# clock.net
KiCad netlist of a schematic drawn in EAGLE
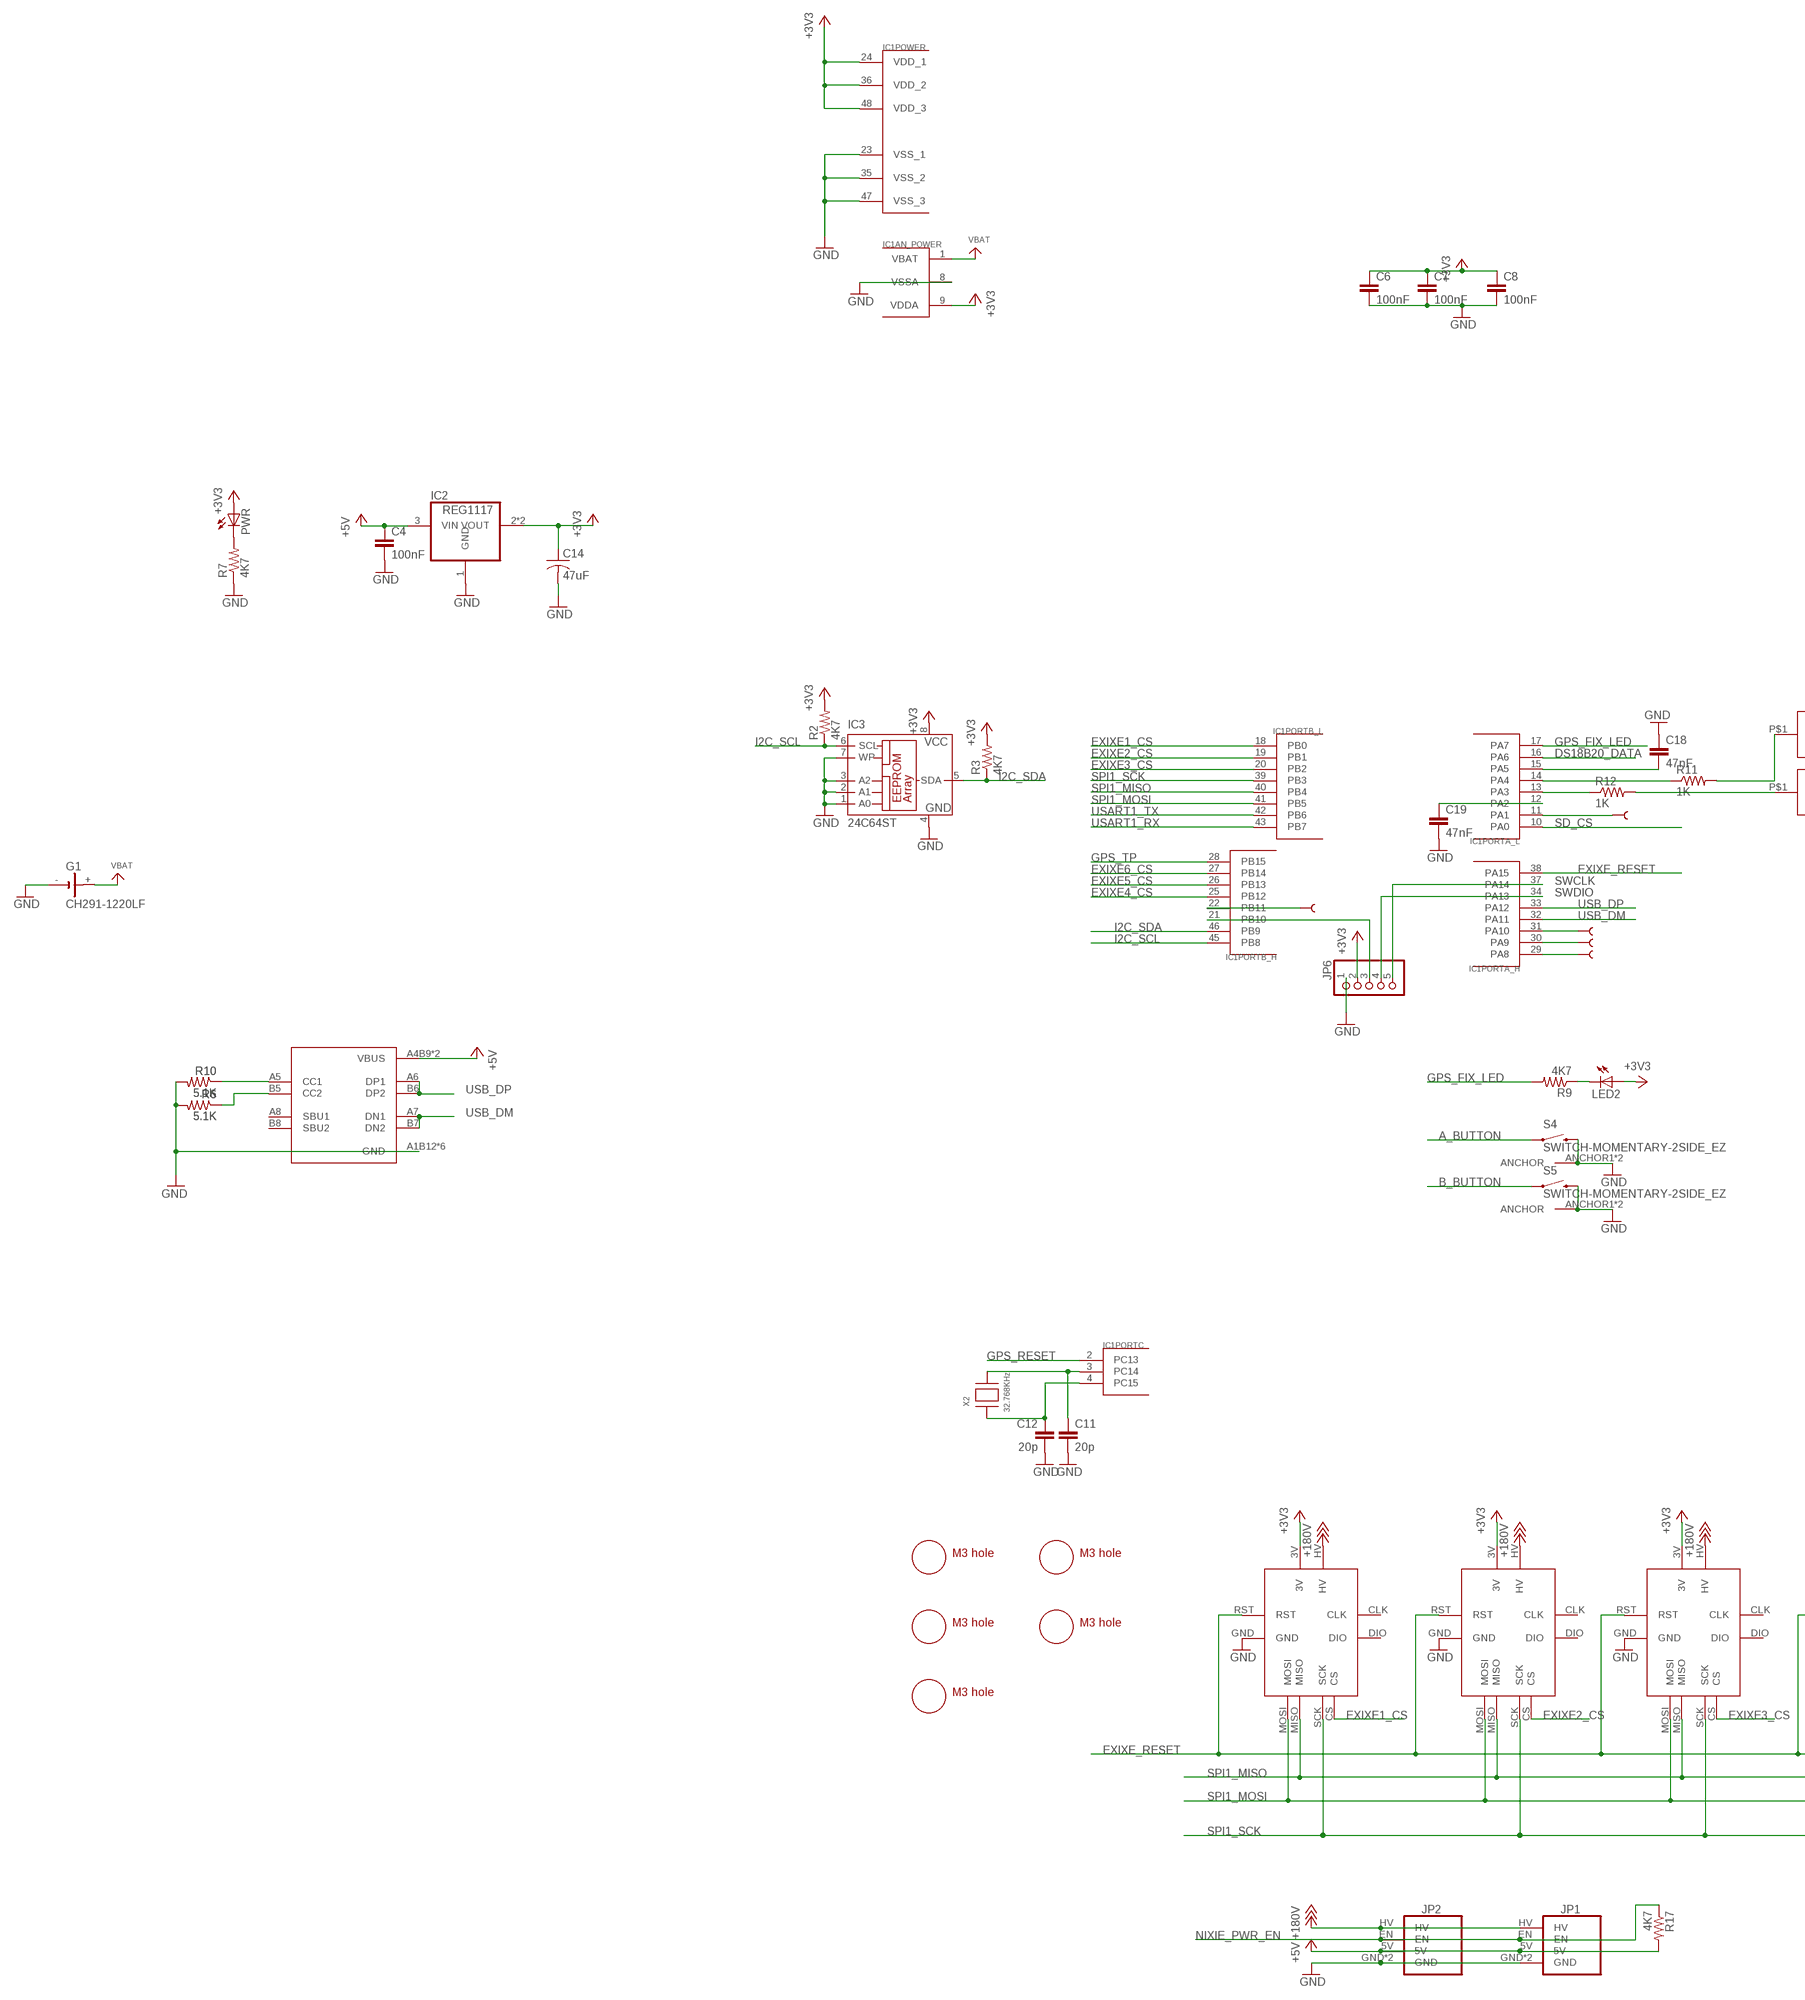
[diagram p0: schematic, sheet 1, part 1 of 2]
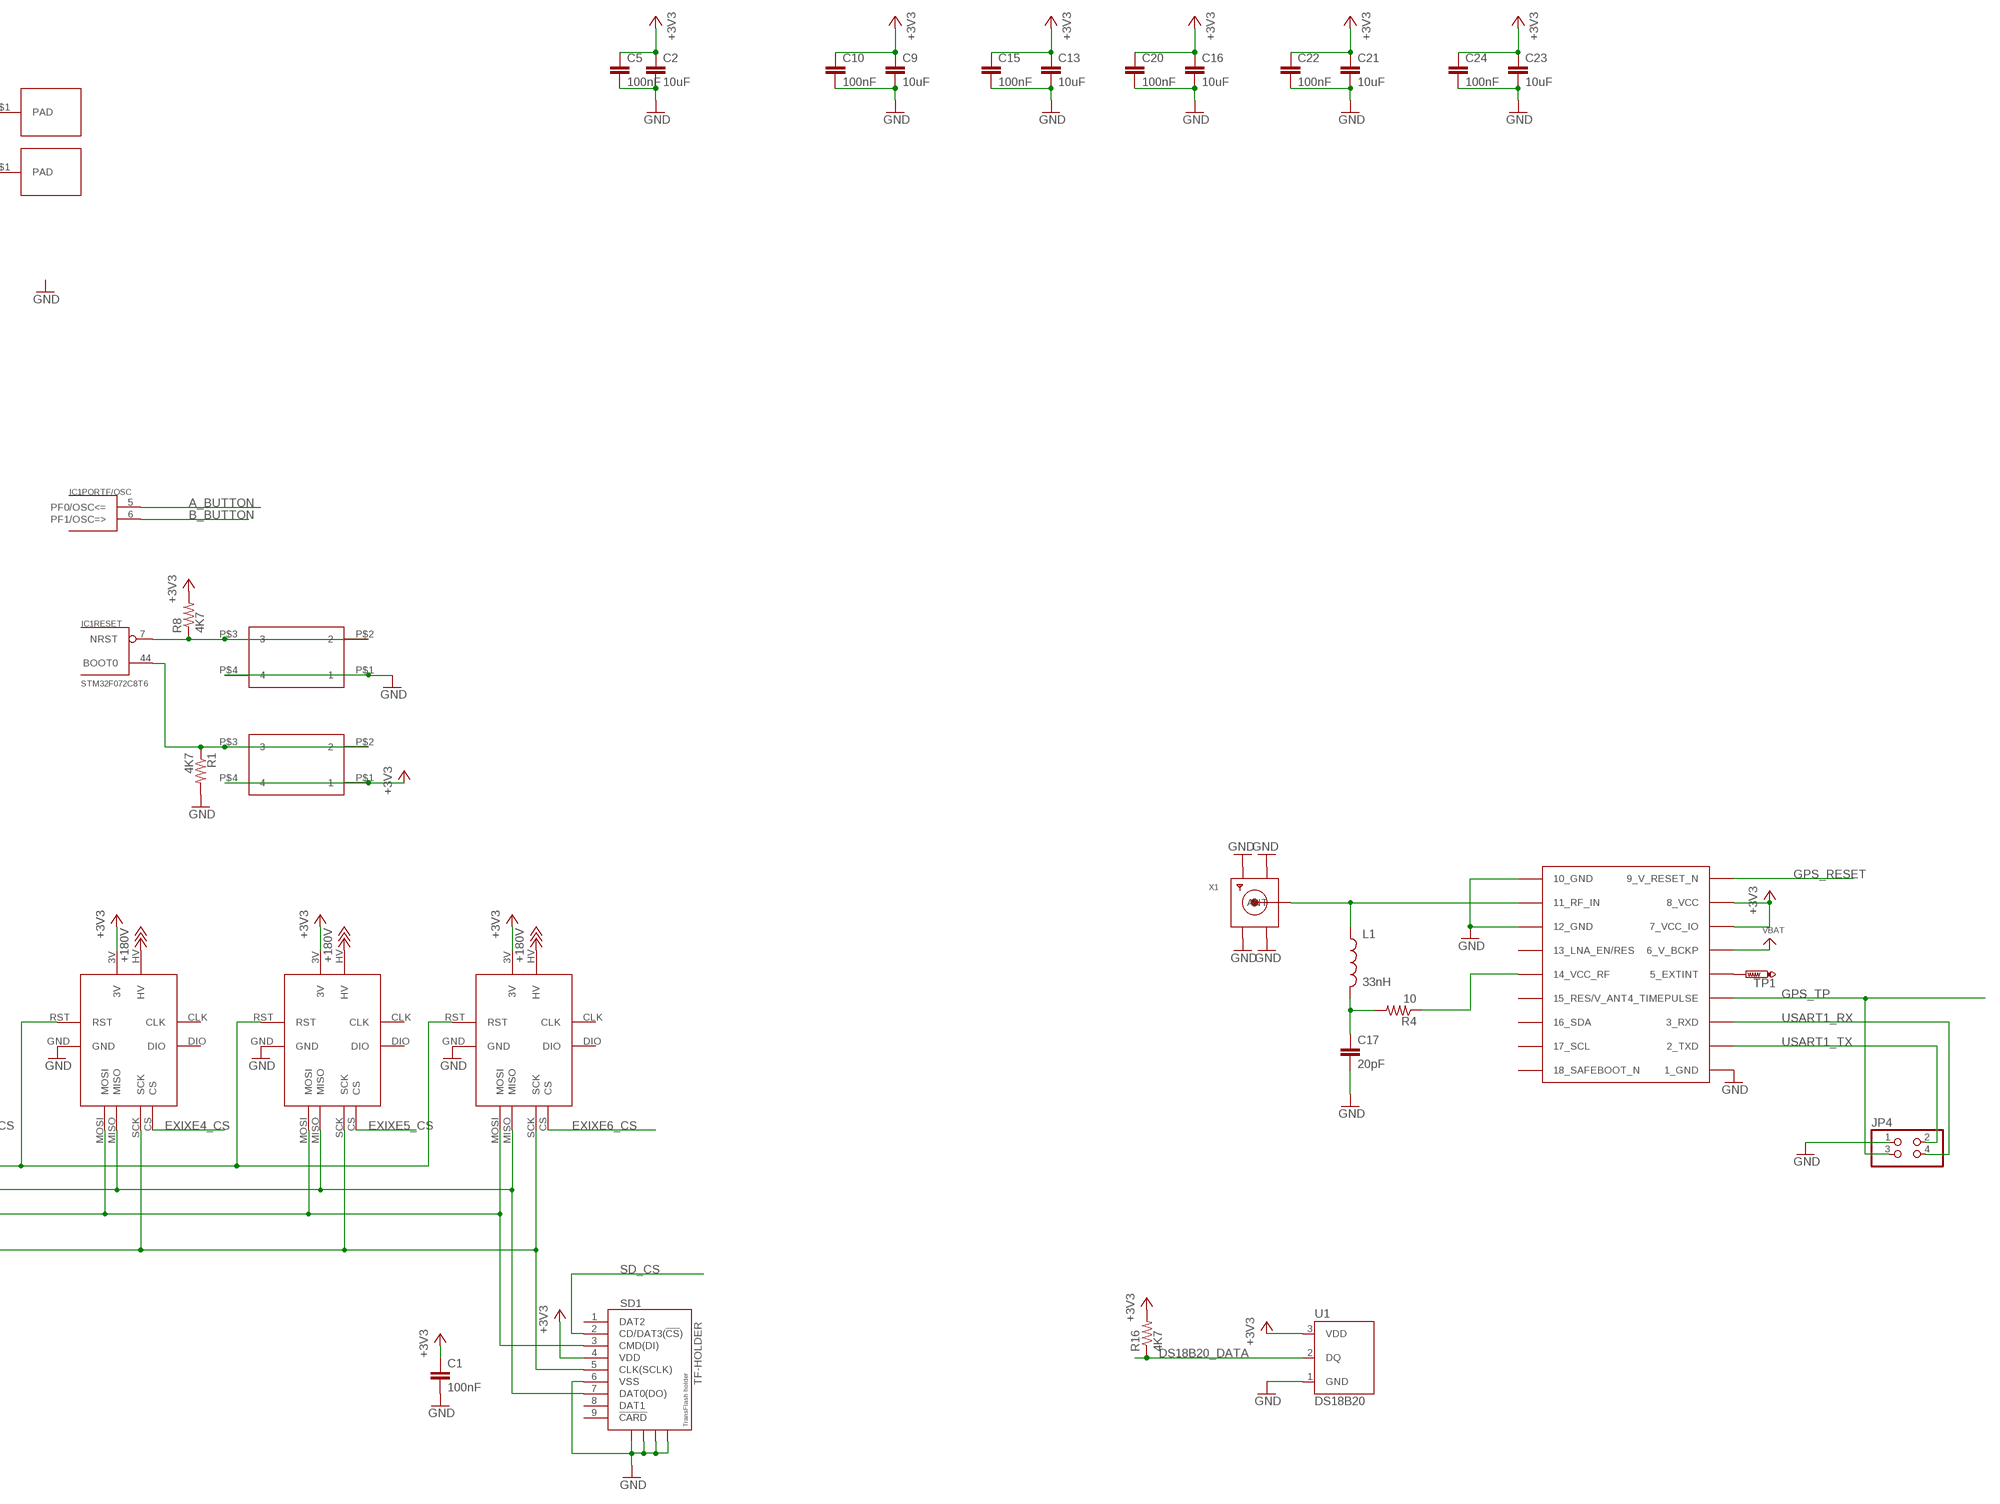
[diagram p1: schematic, sheet 1, part 2 of 2]

(export (version "E")
  (design (tool "Eeschema 10.0.6"))
  (components
    (comp (ref "C1")
      (value "100nF")
      (footprint "eagle-import:0805")
      (libsource (lib "eagle-import") (part "CAP0805"))
    )
    (comp (ref "C2")
      (value "10uF")
      (footprint "eagle-import:0805")
      (libsource (lib "eagle-import") (part "CAP0805"))
    )
    (comp (ref "C4")
      (value "100nF")
      (footprint "eagle-import:0805")
      (libsource (lib "eagle-import") (part "CAP0805"))
    )
    (comp (ref "C5")
      (value "100nF")
      (footprint "eagle-import:0805")
      (libsource (lib "eagle-import") (part "CAP0805"))
    )
    (comp (ref "C6")
      (value "100nF")
      (footprint "eagle-import:0805")
      (libsource (lib "eagle-import") (part "CAP0805"))
    )
    (comp (ref "C7")
      (value "100nF")
      (footprint "eagle-import:0805")
      (libsource (lib "eagle-import") (part "CAP0805"))
    )
    (comp (ref "C8")
      (value "100nF")
      (footprint "eagle-import:0805")
      (libsource (lib "eagle-import") (part "CAP0805"))
    )
    (comp (ref "C9")
      (value "10uF")
      (footprint "eagle-import:0805")
      (libsource (lib "eagle-import") (part "CAP0805"))
    )
    (comp (ref "C10")
      (value "100nF")
      (footprint "eagle-import:0805")
      (libsource (lib "eagle-import") (part "CAP0805"))
    )
    (comp (ref "C11")
      (value "20p")
      (footprint "eagle-import:0805")
      (libsource (lib "eagle-import") (part "CAP0805"))
    )
    (comp (ref "C12")
      (value "20p")
      (footprint "eagle-import:0805")
      (libsource (lib "eagle-import") (part "CAP0805"))
    )
    (comp (ref "C13")
      (value "10uF")
      (footprint "eagle-import:0805")
      (libsource (lib "eagle-import") (part "CAP0805"))
    )
    (comp (ref "C14")
      (value "47uF")
      (footprint "eagle-import:C1210")
      (libsource (lib "eagle-import") (part "C-USC1210"))
    )
    (comp (ref "C15")
      (value "100nF")
      (footprint "eagle-import:0805")
      (libsource (lib "eagle-import") (part "CAP0805"))
    )
    (comp (ref "C16")
      (value "10uF")
      (footprint "eagle-import:0805")
      (libsource (lib "eagle-import") (part "CAP0805"))
    )
    (comp (ref "C17")
      (value "20pF")
      (footprint "eagle-import:0805")
      (libsource (lib "eagle-import") (part "CAP0805"))
    )
    (comp (ref "C18")
      (value "47nF")
      (footprint "eagle-import:0805")
      (libsource (lib "eagle-import") (part "CAP0805"))
    )
    (comp (ref "C19")
      (value "47nF")
      (footprint "eagle-import:0805")
      (libsource (lib "eagle-import") (part "CAP0805"))
    )
    (comp (ref "C20")
      (value "100nF")
      (footprint "eagle-import:0805")
      (libsource (lib "eagle-import") (part "CAP0805"))
    )
    (comp (ref "C21")
      (value "10uF")
      (footprint "eagle-import:0805")
      (libsource (lib "eagle-import") (part "CAP0805"))
    )
    (comp (ref "C22")
      (value "100nF")
      (footprint "eagle-import:0805")
      (libsource (lib "eagle-import") (part "CAP0805"))
    )
    (comp (ref "C23")
      (value "10uF")
      (footprint "eagle-import:0805")
      (libsource (lib "eagle-import") (part "CAP0805"))
    )
    (comp (ref "C24")
      (value "100nF")
      (footprint "eagle-import:0805")
      (libsource (lib "eagle-import") (part "CAP0805"))
    )
    (comp (ref "G1")
      (value "CH291-1220LF")
      (footprint "eagle-import:CH291-1220LF")
      (libsource (lib "eagle-import") (part "CH291-1220LF"))
    )
    (comp (ref "IC1")
      (value "STM32F072C8T6")
      (footprint "eagle-import:TQFP48")
      (libsource (lib "eagle-import") (part "STM32F072C8T6"))
    )
    (comp (ref "IC2")
      (value "REG1117")
      (footprint "eagle-import:SOT223")
      (libsource (lib "eagle-import") (part "REG1117"))
    )
    (comp (ref "IC3")
      (value "24C64ST")
      (footprint "eagle-import:TSSOP8")
      (fields (field (name "MPN") "CAT24C64YI-GT3"))
      (libsource (lib "eagle-import") (part "24STC64"))
    )
    (comp (ref "JP1")
      (value "EBAY_MODULEEBAY")
      (footprint "eagle-import:EBAY_PKG")
      (libsource (lib "eagle-import") (part "EBAY_MODULEEBAY"))
    )
    (comp (ref "JP2")
      (value "EBAY_MODULETAOBAO")
      (footprint "eagle-import:TAOBAO_PKG")
      (libsource (lib "eagle-import") (part "EBAY_MODULETAOBAO"))
    )
    (comp (ref "JP4")
      (value "PINHD-2X2")
      (footprint "eagle-import:2X02")
      (libsource (lib "eagle-import") (part "PINHD-2X2"))
    )
    (comp (ref "JP6")
      (value "PINHD-1X5")
      (footprint "eagle-import:1X05")
      (libsource (lib "eagle-import") (part "PINHD-1X5"))
    )
    (comp (ref "L1")
      (value "33nH")
      (footprint "eagle-import:0805")
      (libsource (lib "eagle-import") (part "INDUCTOR0805"))
    )
    (comp (ref "LED2")
      (value "LEDCHIP-LED0805")
      (footprint "eagle-import:CHIP-LED0805")
      (libsource (lib "eagle-import") (part "LEDCHIP-LED0805"))
    )
    (comp (ref "PWR")
      (value "LEDCHIP-LED0805")
      (footprint "eagle-import:CHIP-LED0805")
      (libsource (lib "eagle-import") (part "LEDCHIP-LED0805"))
    )
    (comp (ref "R1")
      (value "4K7")
      (footprint "eagle-import:0805")
      (libsource (lib "eagle-import") (part "RESISTOR0805-RES"))
    )
    (comp (ref "R2")
      (value "4K7")
      (footprint "eagle-import:0805")
      (libsource (lib "eagle-import") (part "RESISTOR0805-RES"))
    )
    (comp (ref "R3")
      (value "4K7")
      (footprint "eagle-import:0805")
      (libsource (lib "eagle-import") (part "RESISTOR0805-RES"))
    )
    (comp (ref "R4")
      (value "10")
      (footprint "eagle-import:0805")
      (libsource (lib "eagle-import") (part "RESISTOR0805-RES"))
    )
    (comp (ref "R6")
      (value "5.1K")
      (footprint "eagle-import:0805")
      (libsource (lib "eagle-import") (part "joyAnalog_RESISTOR0805-RES"))
    )
    (comp (ref "R7")
      (value "4K7")
      (footprint "eagle-import:0805")
      (libsource (lib "eagle-import") (part "RESISTOR0805-RES"))
    )
    (comp (ref "R8")
      (value "4K7")
      (footprint "eagle-import:0805")
      (libsource (lib "eagle-import") (part "RESISTOR0805-RES"))
    )
    (comp (ref "R9")
      (value "4K7")
      (footprint "eagle-import:0805")
      (libsource (lib "eagle-import") (part "RESISTOR0805-RES"))
    )
    (comp (ref "R10")
      (value "5.1K")
      (footprint "eagle-import:0805")
      (libsource (lib "eagle-import") (part "joyAnalog_RESISTOR0805-RES"))
    )
    (comp (ref "R11")
      (value "1K")
      (footprint "eagle-import:0805")
      (libsource (lib "eagle-import") (part "RESISTOR0805-RES"))
    )
    (comp (ref "R12")
      (value "1K")
      (footprint "eagle-import:0805")
      (libsource (lib "eagle-import") (part "RESISTOR0805-RES"))
    )
    (comp (ref "R16")
      (value "4K7")
      (footprint "eagle-import:0805")
      (libsource (lib "eagle-import") (part "RESISTOR0805-RES"))
    )
    (comp (ref "R17")
      (value "4K7")
      (footprint "eagle-import:0805")
      (libsource (lib "eagle-import") (part "RESISTOR0805-RES"))
    )
    (comp (ref "S4")
      (value "SWITCH-MOMENTARY-2SIDE_EZ")
      (footprint "eagle-import:TACTILE-PTH-SIDEEZ")
      (libsource (lib "eagle-import") (part "SWITCH-MOMENTARY-2SIDE_EZ"))
    )
    (comp (ref "S5")
      (value "SWITCH-MOMENTARY-2SIDE_EZ")
      (footprint "eagle-import:TACTILE-PTH-SIDEEZ")
      (libsource (lib "eagle-import") (part "SWITCH-MOMENTARY-2SIDE_EZ"))
    )
    (comp (ref "SD1")
      (value "TF-HOLDER")
      (footprint "eagle-import:TF-PULL")
      (libsource (lib "eagle-import") (part "TF-HOLDER"))
    )
    (comp (ref "SW1")
      (value "324_SW324_SWITCH_FOOT_HOLE")
      (footprint "eagle-import:342_SWICH_FOOT_HOLE")
      (libsource (lib "eagle-import") (part "324_SW324_SWITCH_FOOT_HOLE"))
    )
    (comp (ref "SW4")
      (value "324_SW324_SWITCH_FOOT_HOLE")
      (footprint "eagle-import:342_SWICH_FOOT_HOLE")
      (libsource (lib "eagle-import") (part "324_SW324_SWITCH_FOOT_HOLE"))
    )
    (comp (ref "TP1")
      (value "PTR1TP20R")
      (footprint "eagle-import:TP20R")
      (libsource (lib "eagle-import") (part "PTR1TP20R"))
    )
    (comp (ref "TP2")
      (value "TEST-POINT3X5")
      (footprint "eagle-import:PAD.03X.05")
      (libsource (lib "eagle-import") (part "TEST-POINT3X5"))
    )
    (comp (ref "TP3")
      (value "TEST-POINT3X5")
      (footprint "eagle-import:PAD.03X.05")
      (libsource (lib "eagle-import") (part "TEST-POINT3X5"))
    )
    (comp (ref "TP4")
      (value "TEST-POINT3X5")
      (footprint "eagle-import:PAD.03X.05")
      (libsource (lib "eagle-import") (part "TEST-POINT3X5"))
    )
    (comp (ref "TP5")
      (value "TEST-POINT3X5")
      (footprint "eagle-import:PAD.03X.05")
      (libsource (lib "eagle-import") (part "TEST-POINT3X5"))
    )
    (comp (ref "TP6")
      (value "TEST-POINT3X5")
      (footprint "eagle-import:PAD.03X.05")
      (libsource (lib "eagle-import") (part "TEST-POINT3X5"))
    )
    (comp (ref "U$1")
      (value "EXIXE")
      (footprint "eagle-import:EXIXE_PAC")
      (libsource (lib "eagle-import") (part "EXIXE"))
    )
    (comp (ref "U$2")
      (value "EXIXE")
      (footprint "eagle-import:EXIXE_PAC")
      (libsource (lib "eagle-import") (part "EXIXE"))
    )
    (comp (ref "U$3")
      (value "EXIXE")
      (footprint "eagle-import:EXIXE_PAC")
      (libsource (lib "eagle-import") (part "EXIXE"))
    )
    (comp (ref "U$4")
      (value "EXIXE")
      (footprint "eagle-import:EXIXE_PAC")
      (libsource (lib "eagle-import") (part "EXIXE"))
    )
    (comp (ref "U$5")
      (value "EXIXE")
      (footprint "eagle-import:EXIXE_PAC")
      (libsource (lib "eagle-import") (part "EXIXE"))
    )
    (comp (ref "U$6")
      (value "EXIXE")
      (footprint "eagle-import:EXIXE_PAC")
      (libsource (lib "eagle-import") (part "EXIXE"))
    )
    (comp (ref "U$7")
      (value "MAX-M8")
      (footprint "eagle-import:MAX-M8")
      (libsource (lib "eagle-import") (part "MAX-M8"))
    )
    (comp (ref "U$10")
      (value "M3_MOUNTING_HOLE")
      (footprint "eagle-import:M3_MOUNTING_HOLE_PACK")
      (libsource (lib "eagle-import") (part "M3_MOUNTING_HOLE"))
    )
    (comp (ref "U$11")
      (value "M3_MOUNTING_HOLE")
      (footprint "eagle-import:M3_MOUNTING_HOLE_PACK")
      (libsource (lib "eagle-import") (part "M3_MOUNTING_HOLE"))
    )
    (comp (ref "U$12")
      (value "M3_MOUNTING_HOLE")
      (footprint "eagle-import:M3_MOUNTING_HOLE_PACK")
      (libsource (lib "eagle-import") (part "M3_MOUNTING_HOLE"))
    )
    (comp (ref "U$13")
      (value "M3_MOUNTING_HOLE")
      (footprint "eagle-import:M3_MOUNTING_HOLE_PACK")
      (libsource (lib "eagle-import") (part "M3_MOUNTING_HOLE"))
    )
    (comp (ref "U$14")
      (value "TOUCHPAD")
      (footprint "eagle-import:TOUCHPAD_PAK")
      (libsource (lib "eagle-import") (part "TOUCHPAD"))
    )
    (comp (ref "U$15")
      (value "TOUCHPAD")
      (footprint "eagle-import:TOUCHPAD_PAK")
      (libsource (lib "eagle-import") (part "TOUCHPAD"))
    )
    (comp (ref "U$20")
      (value "M3_MOUNTING_HOLE")
      (footprint "eagle-import:M3_MOUNTING_HOLE_PACK")
      (libsource (lib "eagle-import") (part "M3_MOUNTING_HOLE"))
    )
    (comp (ref "U1")
      (value "DS18B20")
      (footprint "eagle-import:TO-92-AMMO")
      (libsource (lib "eagle-import") (part "DS18B20"))
    )
    (comp (ref "U2")
      (value "USBC_16P")
      (footprint "eagle-import:USBC_16P_FOOT")
      (libsource (lib "eagle-import") (part "USBC_16P"))
    )
    (comp (ref "X1")
      (value "SMACONNECTOR")
      (footprint "eagle-import:SMA90_DIP")
      (libsource (lib "eagle-import") (part "SMACONNECTOR"))
    )
    (comp (ref "X2")
      (value "32.768KHz")
      (footprint "eagle-import:XTAL3215")
      (libsource (lib "eagle-import") (part "XTAL-3.2X1.5"))
    )
  )
  (nets
    (net (code "1") (name "+3V3") (class "Default")
      (node (ref "C1") (pin "1") (pinfunction "1_1") (pintype "passive"))
      (node (ref "C10") (pin "1") (pinfunction "1_1") (pintype "passive"))
      (node (ref "C13") (pin "1") (pinfunction "1_1") (pintype "passive"))
      (node (ref "C14") (pin "1") (pinfunction "1_1") (pintype "passive"))
      (node (ref "C15") (pin "1") (pinfunction "1_1") (pintype "passive"))
      (node (ref "C16") (pin "1") (pinfunction "1_1") (pintype "passive"))
      (node (ref "C2") (pin "1") (pinfunction "1_1") (pintype "passive"))
      (node (ref "C20") (pin "1") (pinfunction "1_1") (pintype "passive"))
      (node (ref "C21") (pin "1") (pinfunction "1_1") (pintype "passive"))
      (node (ref "C22") (pin "1") (pinfunction "1_1") (pintype "passive"))
      (node (ref "C23") (pin "1") (pinfunction "1_1") (pintype "passive"))
      (node (ref "C24") (pin "1") (pinfunction "1_1") (pintype "passive"))
      (node (ref "C5") (pin "1") (pinfunction "1_1") (pintype "passive"))
      (node (ref "C6") (pin "1") (pinfunction "1_1") (pintype "passive"))
      (node (ref "C7") (pin "1") (pinfunction "1_1") (pintype "passive"))
      (node (ref "C8") (pin "1") (pinfunction "1_1") (pintype "passive"))
      (node (ref "C9") (pin "1") (pinfunction "1_1") (pintype "passive"))
      (node (ref "IC1") (pin "24") (pinfunction "VDD_1_24") (pintype "power_in"))
      (node (ref "IC1") (pin "36") (pinfunction "VDD_2_36") (pintype "power_in"))
      (node (ref "IC1") (pin "48") (pinfunction "VDD_3_48") (pintype "power_in"))
      (node (ref "IC1") (pin "9") (pinfunction "VDDA_9") (pintype "power_in"))
      (node (ref "IC2") (pin "2") (pinfunction "VOUT_2") (pintype "output"))
      (node (ref "IC2") (pin "4") (pinfunction "VOUT_4") (pintype "output"))
      (node (ref "IC3") (pin "8") (pinfunction "VCC_8") (pintype "power_in"))
      (node (ref "JP6") (pin "2") (pinfunction "2_2") (pintype "passive"))
      (node (ref "LED2") (pin "A") (pinfunction "A_A") (pintype "passive"))
      (node (ref "PWR") (pin "A") (pinfunction "A_A") (pintype "passive"))
      (node (ref "R16") (pin "2") (pinfunction "2_2") (pintype "passive"))
      (node (ref "R2") (pin "2") (pinfunction "2_2") (pintype "passive"))
      (node (ref "R3") (pin "2") (pinfunction "2_2") (pintype "passive"))
      (node (ref "R8") (pin "2") (pinfunction "2_2") (pintype "passive"))
      (node (ref "SD1") (pin "4") (pinfunction "VDD_4") (pintype "power_in"))
      (node (ref "SW1") (pin "P$1") (pinfunction "1_P$1") (pintype "bidirectional"))
      (node (ref "SW1") (pin "P$4") (pinfunction "4_P$4") (pintype "bidirectional"))
      (node (ref "U$1") (pin "3V") (pinfunction "3V_3V") (pintype "bidirectional"))
      (node (ref "U$2") (pin "3V") (pinfunction "3V_3V") (pintype "bidirectional"))
      (node (ref "U$3") (pin "3V") (pinfunction "3V_3V") (pintype "bidirectional"))
      (node (ref "U$4") (pin "3V") (pinfunction "3V_3V") (pintype "bidirectional"))
      (node (ref "U$5") (pin "3V") (pinfunction "3V_3V") (pintype "bidirectional"))
      (node (ref "U$6") (pin "3V") (pinfunction "3V_3V") (pintype "bidirectional"))
      (node (ref "U$7") (pin "7_VCC_IO") (pinfunction "7_VCC_IO_7_VCC_IO") (pintype "power_in"))
      (node (ref "U$7") (pin "8_VCC") (pinfunction "8_VCC_8_VCC") (pintype "power_in"))
      (node (ref "U1") (pin "3") (pinfunction "VDD_3") (pintype "power_in"))
    )
    (net (code "2") (name "+5V") (class "Default")
      (node (ref "C4") (pin "1") (pinfunction "1_1") (pintype "passive"))
      (node (ref "IC2") (pin "3") (pinfunction "VIN_3") (pintype "input"))
      (node (ref "JP1") (pin "5V") (pinfunction "5V_5V") (pintype "bidirectional"))
      (node (ref "JP2") (pin "5V") (pinfunction "5V_5V") (pintype "bidirectional"))
      (node (ref "R17") (pin "2") (pinfunction "2_2") (pintype "passive"))
      (node (ref "U2") (pin "A4B9") (pinfunction "VBUS_A4B9") (pintype "bidirectional"))
      (node (ref "U2") (pin "B4A9") (pinfunction "VBUS_B4A9") (pintype "bidirectional"))
    )
    (net (code "3") (name "+180V") (class "Default")
      (node (ref "JP1") (pin "HV") (pinfunction "HV_HV") (pintype "bidirectional"))
      (node (ref "JP2") (pin "HV") (pinfunction "HV_HV") (pintype "bidirectional"))
      (node (ref "U$1") (pin "HV") (pinfunction "HV_HV") (pintype "bidirectional"))
      (node (ref "U$2") (pin "HV") (pinfunction "HV_HV") (pintype "bidirectional"))
      (node (ref "U$3") (pin "HV") (pinfunction "HV_HV") (pintype "bidirectional"))
      (node (ref "U$4") (pin "HV") (pinfunction "HV_HV") (pintype "bidirectional"))
      (node (ref "U$5") (pin "HV") (pinfunction "HV_HV") (pintype "bidirectional"))
      (node (ref "U$6") (pin "HV") (pinfunction "HV_HV") (pintype "bidirectional"))
    )
    (net (code "4") (name "/A_BUTTON") (class "Default")
      (node (ref "IC1") (pin "5") (pinfunction "PF0/OSC<=_5") (pintype "bidirectional"))
      (node (ref "S4") (pin "1") (pinfunction "1_1") (pintype "passive"))
    )
    (net (code "5") (name "/B_BUTTON") (class "Default")
      (node (ref "IC1") (pin "6") (pinfunction "PF1/OSC=>_6") (pintype "bidirectional"))
      (node (ref "S5") (pin "1") (pinfunction "1_1") (pintype "passive"))
    )
    (net (code "6") (name "/DS18B20_DATA") (class "Default")
      (node (ref "IC1") (pin "16") (pinfunction "PA6_16") (pintype "bidirectional"))
      (node (ref "R16") (pin "1") (pinfunction "1_1") (pintype "passive"))
      (node (ref "U1") (pin "2") (pinfunction "DQ_2") (pintype "bidirectional"))
    )
    (net (code "7") (name "/EXIXE1_CS") (class "Default")
      (node (ref "IC1") (pin "18") (pinfunction "PB0_18") (pintype "bidirectional"))
      (node (ref "U$1") (pin "CS") (pinfunction "CS_CS") (pintype "bidirectional"))
    )
    (net (code "8") (name "/EXIXE2_CS") (class "Default")
      (node (ref "IC1") (pin "19") (pinfunction "PB1_19") (pintype "bidirectional"))
      (node (ref "U$2") (pin "CS") (pinfunction "CS_CS") (pintype "bidirectional"))
    )
    (net (code "9") (name "/EXIXE3_CS") (class "Default")
      (node (ref "IC1") (pin "20") (pinfunction "PB2_20") (pintype "bidirectional"))
      (node (ref "U$3") (pin "CS") (pinfunction "CS_CS") (pintype "bidirectional"))
    )
    (net (code "10") (name "/EXIXE4_CS") (class "Default")
      (node (ref "IC1") (pin "25") (pinfunction "PB12_25") (pintype "bidirectional"))
      (node (ref "U$4") (pin "CS") (pinfunction "CS_CS") (pintype "bidirectional"))
    )
    (net (code "11") (name "/EXIXE5_CS") (class "Default")
      (node (ref "IC1") (pin "26") (pinfunction "PB13_26") (pintype "bidirectional"))
      (node (ref "U$5") (pin "CS") (pinfunction "CS_CS") (pintype "bidirectional"))
    )
    (net (code "12") (name "/EXIXE6_CS") (class "Default")
      (node (ref "IC1") (pin "27") (pinfunction "PB14_27") (pintype "bidirectional"))
      (node (ref "U$6") (pin "CS") (pinfunction "CS_CS") (pintype "bidirectional"))
    )
    (net (code "13") (name "/EXIXE_RESET") (class "Default")
      (node (ref "IC1") (pin "38") (pinfunction "PA15_38") (pintype "bidirectional"))
      (node (ref "U$1") (pin "RST") (pinfunction "RST_RST") (pintype "bidirectional"))
      (node (ref "U$2") (pin "RST") (pinfunction "RST_RST") (pintype "bidirectional"))
      (node (ref "U$3") (pin "RST") (pinfunction "RST_RST") (pintype "bidirectional"))
      (node (ref "U$4") (pin "RST") (pinfunction "RST_RST") (pintype "bidirectional"))
      (node (ref "U$5") (pin "RST") (pinfunction "RST_RST") (pintype "bidirectional"))
      (node (ref "U$6") (pin "RST") (pinfunction "RST_RST") (pintype "bidirectional"))
    )
    (net (code "14") (name "/GPS_FIX_LED") (class "Default")
      (node (ref "IC1") (pin "17") (pinfunction "PA7_17") (pintype "bidirectional"))
      (node (ref "R9") (pin "2") (pinfunction "2_2") (pintype "passive"))
    )
    (net (code "15") (name "/GPS_RESET") (class "Default")
      (node (ref "IC1") (pin "2") (pinfunction "PC13_2") (pintype "bidirectional"))
      (node (ref "U$7") (pin "9_RESET_N") (pinfunction "9_V_RESET_N_9_RESET_N") (pintype "power_in"))
    )
    (net (code "16") (name "/GPS_TP") (class "Default")
      (node (ref "IC1") (pin "28") (pinfunction "PB15_28") (pintype "bidirectional"))
      (node (ref "JP4") (pin "3") (pinfunction "3_3") (pintype "passive"))
      (node (ref "U$7") (pin "4_TIMEPULSE") (pinfunction "4_TIMEPULSE_4_TIMEPULSE") (pintype "bidirectional"))
    )
    (net (code "17") (name "/I2C_SCL") (class "Default")
      (node (ref "IC1") (pin "45") (pinfunction "PB8_45") (pintype "bidirectional"))
      (node (ref "IC3") (pin "6") (pinfunction "SCL_6") (pintype "input"))
      (node (ref "R2") (pin "1") (pinfunction "1_1") (pintype "passive"))
    )
    (net (code "18") (name "/I2C_SDA") (class "Default")
      (node (ref "IC1") (pin "46") (pinfunction "PB9_46") (pintype "bidirectional"))
      (node (ref "IC3") (pin "5") (pinfunction "SDA_5") (pintype "bidirectional"))
      (node (ref "R3") (pin "1") (pinfunction "1_1") (pintype "passive"))
    )
    (net (code "19") (name "/NIXIE_PWR_EN") (class "Default")
      (node (ref "JP1") (pin "EN") (pinfunction "EN_EN") (pintype "bidirectional"))
      (node (ref "JP2") (pin "EN") (pinfunction "EN_EN") (pintype "bidirectional"))
      (node (ref "R17") (pin "1") (pinfunction "1_1") (pintype "passive"))
    )
    (net (code "20") (name "/SD_CS") (class "Default")
      (node (ref "IC1") (pin "10") (pinfunction "PA0_10") (pintype "bidirectional"))
      (node (ref "SD1") (pin "2") (pinfunction "CD/DAT3(~{CS})_2") (pintype "bidirectional"))
    )
    (net (code "21") (name "/SPI1_MISO") (class "Default")
      (node (ref "IC1") (pin "40") (pinfunction "PB4_40") (pintype "bidirectional"))
      (node (ref "SD1") (pin "7") (pinfunction "DAT0(DO)_7") (pintype "bidirectional"))
      (node (ref "U$1") (pin "MISO") (pinfunction "MISO_MISO") (pintype "bidirectional"))
      (node (ref "U$2") (pin "MISO") (pinfunction "MISO_MISO") (pintype "bidirectional"))
      (node (ref "U$3") (pin "MISO") (pinfunction "MISO_MISO") (pintype "bidirectional"))
      (node (ref "U$4") (pin "MISO") (pinfunction "MISO_MISO") (pintype "bidirectional"))
      (node (ref "U$5") (pin "MISO") (pinfunction "MISO_MISO") (pintype "bidirectional"))
      (node (ref "U$6") (pin "MISO") (pinfunction "MISO_MISO") (pintype "bidirectional"))
    )
    (net (code "22") (name "/SPI1_MOSI") (class "Default")
      (node (ref "IC1") (pin "41") (pinfunction "PB5_41") (pintype "bidirectional"))
      (node (ref "SD1") (pin "3") (pinfunction "CMD(DI)_3") (pintype "bidirectional"))
      (node (ref "U$1") (pin "MOSI") (pinfunction "MOSI_MOSI") (pintype "bidirectional"))
      (node (ref "U$2") (pin "MOSI") (pinfunction "MOSI_MOSI") (pintype "bidirectional"))
      (node (ref "U$3") (pin "MOSI") (pinfunction "MOSI_MOSI") (pintype "bidirectional"))
      (node (ref "U$4") (pin "MOSI") (pinfunction "MOSI_MOSI") (pintype "bidirectional"))
      (node (ref "U$5") (pin "MOSI") (pinfunction "MOSI_MOSI") (pintype "bidirectional"))
      (node (ref "U$6") (pin "MOSI") (pinfunction "MOSI_MOSI") (pintype "bidirectional"))
    )
    (net (code "23") (name "/SPI1_SCK") (class "Default")
      (node (ref "IC1") (pin "39") (pinfunction "PB3_39") (pintype "bidirectional"))
      (node (ref "SD1") (pin "5") (pinfunction "CLK(SCLK)_5") (pintype "input"))
      (node (ref "U$1") (pin "SCK") (pinfunction "SCK_SCK") (pintype "bidirectional"))
      (node (ref "U$2") (pin "SCK") (pinfunction "SCK_SCK") (pintype "bidirectional"))
      (node (ref "U$3") (pin "SCK") (pinfunction "SCK_SCK") (pintype "bidirectional"))
      (node (ref "U$4") (pin "SCK") (pinfunction "SCK_SCK") (pintype "bidirectional"))
      (node (ref "U$5") (pin "SCK") (pinfunction "SCK_SCK") (pintype "bidirectional"))
      (node (ref "U$6") (pin "SCK") (pinfunction "SCK_SCK") (pintype "bidirectional"))
    )
    (net (code "24") (name "/SWCLK") (class "Default")
      (node (ref "IC1") (pin "37") (pinfunction "PA14_37") (pintype "bidirectional"))
      (node (ref "JP6") (pin "5") (pinfunction "5_5") (pintype "passive"))
    )
    (net (code "25") (name "/SWDIO") (class "Default")
      (node (ref "IC1") (pin "34") (pinfunction "PA13_34") (pintype "bidirectional"))
      (node (ref "JP6") (pin "4") (pinfunction "4_4") (pintype "passive"))
    )
    (net (code "26") (name "/USART1_RX") (class "Default")
      (node (ref "IC1") (pin "43") (pinfunction "PB7_43") (pintype "bidirectional"))
      (node (ref "JP4") (pin "4") (pinfunction "4_4") (pintype "passive"))
      (node (ref "U$7") (pin "3_RXD") (pinfunction "3_RXD_3_RXD") (pintype "bidirectional"))
    )
    (net (code "27") (name "/USART1_TX") (class "Default")
      (node (ref "IC1") (pin "42") (pinfunction "PB6_42") (pintype "bidirectional"))
      (node (ref "JP4") (pin "2") (pinfunction "2_2") (pintype "passive"))
      (node (ref "U$7") (pin "2_TXD") (pinfunction "2_TXD_2_TXD") (pintype "bidirectional"))
    )
    (net (code "28") (name "/USB_DM") (class "Default")
      (node (ref "IC1") (pin "32") (pinfunction "PA11_32") (pintype "bidirectional"))
      (node (ref "U2") (pin "A7") (pinfunction "DN1_A7") (pintype "bidirectional"))
      (node (ref "U2") (pin "B7") (pinfunction "DN2_B7") (pintype "bidirectional"))
    )
    (net (code "29") (name "/USB_DP") (class "Default")
      (node (ref "IC1") (pin "33") (pinfunction "PA12_33") (pintype "bidirectional"))
      (node (ref "U2") (pin "A6") (pinfunction "DP1_A6") (pintype "bidirectional"))
      (node (ref "U2") (pin "B6") (pinfunction "DP2_B6") (pintype "bidirectional"))
    )
    (net (code "30") (name "GND") (class "Default")
      (node (ref "C1") (pin "2") (pinfunction "2_2") (pintype "passive"))
      (node (ref "C10") (pin "2") (pinfunction "2_2") (pintype "passive"))
      (node (ref "C11") (pin "2") (pinfunction "2_2") (pintype "passive"))
      (node (ref "C12") (pin "2") (pinfunction "2_2") (pintype "passive"))
      (node (ref "C13") (pin "2") (pinfunction "2_2") (pintype "passive"))
      (node (ref "C14") (pin "2") (pinfunction "2_2") (pintype "passive"))
      (node (ref "C15") (pin "2") (pinfunction "2_2") (pintype "passive"))
      (node (ref "C16") (pin "2") (pinfunction "2_2") (pintype "passive"))
      (node (ref "C17") (pin "2") (pinfunction "2_2") (pintype "passive"))
      (node (ref "C18") (pin "1") (pinfunction "1_1") (pintype "passive"))
      (node (ref "C19") (pin "2") (pinfunction "2_2") (pintype "passive"))
      (node (ref "C2") (pin "2") (pinfunction "2_2") (pintype "passive"))
      (node (ref "C20") (pin "2") (pinfunction "2_2") (pintype "passive"))
      (node (ref "C21") (pin "2") (pinfunction "2_2") (pintype "passive"))
      (node (ref "C22") (pin "2") (pinfunction "2_2") (pintype "passive"))
      (node (ref "C23") (pin "2") (pinfunction "2_2") (pintype "passive"))
      (node (ref "C24") (pin "2") (pinfunction "2_2") (pintype "passive"))
      (node (ref "C4") (pin "2") (pinfunction "2_2") (pintype "passive"))
      (node (ref "C5") (pin "2") (pinfunction "2_2") (pintype "passive"))
      (node (ref "C6") (pin "2") (pinfunction "2_2") (pintype "passive"))
      (node (ref "C7") (pin "2") (pinfunction "2_2") (pintype "passive"))
      (node (ref "C8") (pin "2") (pinfunction "2_2") (pintype "passive"))
      (node (ref "C9") (pin "2") (pinfunction "2_2") (pintype "passive"))
      (node (ref "G1") (pin "-") (pinfunction "-_-") (pintype "passive"))
      (node (ref "IC1") (pin "23") (pinfunction "VSS_1_23") (pintype "power_in"))
      (node (ref "IC1") (pin "35") (pinfunction "VSS_2_35") (pintype "power_in"))
      (node (ref "IC1") (pin "47") (pinfunction "VSS_3_47") (pintype "power_in"))
      (node (ref "IC1") (pin "8") (pinfunction "VSSA_8") (pintype "power_in"))
      (node (ref "IC2") (pin "1") (pinfunction "GND_1") (pintype "power_in"))
      (node (ref "IC3") (pin "1") (pinfunction "A0_1") (pintype "input"))
      (node (ref "IC3") (pin "2") (pinfunction "A1_2") (pintype "input"))
      (node (ref "IC3") (pin "3") (pinfunction "A2_3") (pintype "input"))
      (node (ref "IC3") (pin "4") (pinfunction "GND_4") (pintype "power_in"))
      (node (ref "IC3") (pin "7") (pinfunction "WP_7") (pintype "input"))
      (node (ref "JP1") (pin "GND") (pinfunction "GND_GND") (pintype "bidirectional"))
      (node (ref "JP1") (pin "GND2") (pinfunction "GND_GND2") (pintype "bidirectional"))
      (node (ref "JP2") (pin "GND") (pinfunction "GND_GND") (pintype "bidirectional"))
      (node (ref "JP2") (pin "GND2") (pinfunction "GND_GND2") (pintype "bidirectional"))
      (node (ref "JP4") (pin "1") (pinfunction "1_1") (pintype "passive"))
      (node (ref "JP6") (pin "1") (pinfunction "1_1") (pintype "passive"))
      (node (ref "R1") (pin "2") (pinfunction "2_2") (pintype "passive"))
      (node (ref "R10") (pin "2") (pinfunction "2_2") (pintype "passive"))
      (node (ref "R6") (pin "2") (pinfunction "2_2") (pintype "passive"))
      (node (ref "R7") (pin "1") (pinfunction "1_1") (pintype "passive"))
      (node (ref "S4") (pin "2") (pinfunction "2_2") (pintype "passive"))
      (node (ref "S4") (pin "ANCHOR1") (pinfunction "ANCHOR_ANCHOR1") (pintype "bidirectional"))
      (node (ref "S4") (pin "ANCHOR2") (pinfunction "ANCHOR_ANCHOR2") (pintype "bidirectional"))
      (node (ref "S5") (pin "2") (pinfunction "2_2") (pintype "passive"))
      (node (ref "S5") (pin "ANCHOR1") (pinfunction "ANCHOR_ANCHOR1") (pintype "bidirectional"))
      (node (ref "S5") (pin "ANCHOR2") (pinfunction "ANCHOR_ANCHOR2") (pintype "bidirectional"))
      (node (ref "SD1") (pin "6") (pinfunction "VSS_6") (pintype "power_in"))
      (node (ref "SD1") (pin "S1") (pinfunction "S1_S1") (pintype "passive"))
      (node (ref "SD1") (pin "S2") (pinfunction "S2_S2") (pintype "passive"))
      (node (ref "SD1") (pin "S3") (pinfunction "S3_S3") (pintype "passive"))
      (node (ref "SD1") (pin "S4") (pinfunction "S4_S4") (pintype "passive"))
      (node (ref "SW4") (pin "P$1") (pinfunction "1_P$1") (pintype "bidirectional"))
      (node (ref "SW4") (pin "P$4") (pinfunction "4_P$4") (pintype "bidirectional"))
      (node (ref "U$1") (pin "GND") (pinfunction "GND_GND") (pintype "bidirectional"))
      (node (ref "U$2") (pin "GND") (pinfunction "GND_GND") (pintype "bidirectional"))
      (node (ref "U$3") (pin "GND") (pinfunction "GND_GND") (pintype "bidirectional"))
      (node (ref "U$4") (pin "GND") (pinfunction "GND_GND") (pintype "bidirectional"))
      (node (ref "U$5") (pin "GND") (pinfunction "GND_GND") (pintype "bidirectional"))
      (node (ref "U$6") (pin "GND") (pinfunction "GND_GND") (pintype "bidirectional"))
      (node (ref "U$7") (pin "10_GND") (pinfunction "10_GND_10_GND") (pintype "power_in"))
      (node (ref "U$7") (pin "12_GND") (pinfunction "12_GND_12_GND") (pintype "power_in"))
      (node (ref "U$7") (pin "1_GND") (pinfunction "1_GND_1_GND") (pintype "power_in"))
      (node (ref "U1") (pin "1") (pinfunction "GND_1") (pintype "power_in"))
      (node (ref "U2") (pin "A1B12") (pinfunction "GND_A1B12") (pintype "bidirectional"))
      (node (ref "U2") (pin "B11A12") (pinfunction "GND_B11A12") (pintype "bidirectional"))
      (node (ref "U2") (pin "P$13") (pinfunction "GND_P$13") (pintype "bidirectional"))
      (node (ref "U2") (pin "P$14") (pinfunction "GND_P$14") (pintype "bidirectional"))
      (node (ref "U2") (pin "P$15") (pinfunction "GND_P$15") (pintype "bidirectional"))
      (node (ref "U2") (pin "P$16") (pinfunction "GND_P$16") (pintype "bidirectional"))
      (node (ref "X1") (pin "GND1") (pinfunction "GND1_GND1") (pintype "power_in"))
      (node (ref "X1") (pin "GND2") (pinfunction "GND2_GND2") (pintype "power_in"))
      (node (ref "X1") (pin "GND3") (pinfunction "GND3_GND3") (pintype "power_in"))
      (node (ref "X1") (pin "GND4") (pinfunction "GND4_GND4") (pintype "power_in"))
    )
    (net (code "31") (name "Net-(C17-Pad1)") (class "Default")
      (node (ref "C17") (pin "1") (pinfunction "1_1") (pintype "passive"))
      (node (ref "L1") (pin "2") (pinfunction "2_2") (pintype "passive"))
      (node (ref "R4") (pin "2") (pinfunction "2_2") (pintype "passive"))
    )
    (net (code "32") (name "Net-(IC1B-PA8)") (class "Default")
      (node (ref "IC1") (pin "29") (pinfunction "PA8_29") (pintype "bidirectional"))
      (node (ref "TP4") (pin "P$1") (pinfunction "1_P$1") (pintype "bidirectional"))
    )
    (net (code "33") (name "Net-(IC1B-PA9)") (class "Default")
      (node (ref "IC1") (pin "30") (pinfunction "PA9_30") (pintype "bidirectional"))
      (node (ref "TP3") (pin "P$1") (pinfunction "1_P$1") (pintype "bidirectional"))
    )
    (net (code "34") (name "Net-(IC1B-PA10)") (class "Default")
      (node (ref "IC1") (pin "31") (pinfunction "PA10_31") (pintype "bidirectional"))
      (node (ref "TP2") (pin "P$1") (pinfunction "1_P$1") (pintype "bidirectional"))
    )
    (net (code "35") (name "Net-(IC1C-PA1)") (class "Default")
      (node (ref "IC1") (pin "11") (pinfunction "PA1_11") (pintype "bidirectional"))
      (node (ref "TP6") (pin "P$1") (pinfunction "1_P$1") (pintype "bidirectional"))
    )
    (net (code "36") (name "Net-(IC1C-PA2)") (class "Default")
      (node (ref "C19") (pin "1") (pinfunction "1_1") (pintype "passive"))
      (node (ref "IC1") (pin "12") (pinfunction "PA2_12") (pintype "bidirectional"))
    )
    (net (code "37") (name "Net-(IC1C-PA3)") (class "Default")
      (node (ref "IC1") (pin "13") (pinfunction "PA3_13") (pintype "bidirectional"))
      (node (ref "R12") (pin "1") (pinfunction "1_1") (pintype "passive"))
    )
    (net (code "38") (name "Net-(IC1C-PA4)") (class "Default")
      (node (ref "IC1") (pin "14") (pinfunction "PA4_14") (pintype "bidirectional"))
      (node (ref "R11") (pin "1") (pinfunction "1_1") (pintype "passive"))
    )
    (net (code "39") (name "Net-(IC1C-PA5)") (class "Default")
      (node (ref "C18") (pin "2") (pinfunction "2_2") (pintype "passive"))
      (node (ref "IC1") (pin "15") (pinfunction "PA5_15") (pintype "bidirectional"))
    )
    (net (code "40") (name "Net-(IC1D-PB10)") (class "Default")
      (node (ref "IC1") (pin "21") (pinfunction "PB10_21") (pintype "bidirectional"))
      (node (ref "JP6") (pin "3") (pinfunction "3_3") (pintype "passive"))
    )
    (net (code "41") (name "Net-(IC1D-PB11)") (class "Default")
      (node (ref "IC1") (pin "22") (pinfunction "PB11_22") (pintype "bidirectional"))
      (node (ref "TP5") (pin "P$1") (pinfunction "1_P$1") (pintype "bidirectional"))
    )
    (net (code "42") (name "Net-(IC1F-PC14)") (class "Default")
      (node (ref "C11") (pin "1") (pinfunction "1_1") (pintype "passive"))
      (node (ref "IC1") (pin "3") (pinfunction "PC14_3") (pintype "bidirectional"))
      (node (ref "X2") (pin "P$2") (pinfunction "P$2_P$2") (pintype "bidirectional"))
    )
    (net (code "43") (name "Net-(IC1F-PC15)") (class "Default")
      (node (ref "C12") (pin "1") (pinfunction "1_1") (pintype "passive"))
      (node (ref "IC1") (pin "4") (pinfunction "PC15_4") (pintype "bidirectional"))
      (node (ref "X2") (pin "P$1") (pinfunction "P$1_P$1") (pintype "bidirectional"))
    )
    (net (code "44") (name "Net-(IC1I-BOOT0)") (class "Default")
      (node (ref "IC1") (pin "44") (pinfunction "BOOT0_44") (pintype "input"))
      (node (ref "R1") (pin "1") (pinfunction "1_1") (pintype "passive"))
      (node (ref "SW1") (pin "P$2") (pinfunction "2_P$2") (pintype "bidirectional"))
      (node (ref "SW1") (pin "P$3") (pinfunction "3_P$3") (pintype "bidirectional"))
    )
    (net (code "45") (name "Net-(IC1I-NRST)") (class "Default")
      (node (ref "IC1") (pin "7") (pinfunction "NRST_7") (pintype "input"))
      (node (ref "R8") (pin "1") (pinfunction "1_1") (pintype "passive"))
      (node (ref "SW4") (pin "P$2") (pinfunction "2_P$2") (pintype "bidirectional"))
      (node (ref "SW4") (pin "P$3") (pinfunction "3_P$3") (pintype "bidirectional"))
    )
    (net (code "46") (name "Net-(LED2-PadC)") (class "Default")
      (node (ref "LED2") (pin "C") (pinfunction "C_C") (pintype "passive"))
      (node (ref "R9") (pin "1") (pinfunction "1_1") (pintype "passive"))
    )
    (net (code "47") (name "Net-(PWR-PadC)") (class "Default")
      (node (ref "PWR") (pin "C") (pinfunction "C_C") (pintype "passive"))
      (node (ref "R7") (pin "2") (pinfunction "2_2") (pintype "passive"))
    )
    (net (code "48") (name "Net-(R4-Pad1)") (class "Default")
      (node (ref "R4") (pin "1") (pinfunction "1_1") (pintype "passive"))
      (node (ref "U$7") (pin "14_VCC_RF") (pinfunction "14_VCC_RF_14_VCC_RF") (pintype "bidirectional"))
    )
    (net (code "49") (name "Net-(TP1-PadTP)") (class "Default")
      (node (ref "TP1") (pin "TP") (pinfunction "TP_TP") (pintype "input"))
      (node (ref "U$7") (pin "5_EXTINT") (pinfunction "5_EXTINT_5_EXTINT") (pintype "bidirectional"))
    )
    (net (code "50") (name "Net-(U$14-PAD)") (class "Default")
      (node (ref "R12") (pin "2") (pinfunction "2_2") (pintype "passive"))
      (node (ref "U$14") (pin "P$1") (pinfunction "PAD_P$1") (pintype "bidirectional"))
    )
    (net (code "51") (name "Net-(U$15-PAD)") (class "Default")
      (node (ref "R11") (pin "2") (pinfunction "2_2") (pintype "passive"))
      (node (ref "U$15") (pin "P$1") (pinfunction "PAD_P$1") (pintype "bidirectional"))
    )
    (net (code "52") (name "Net-(U2-CC1)") (class "Default")
      (node (ref "R10") (pin "1") (pinfunction "1_1") (pintype "passive"))
      (node (ref "U2") (pin "A5") (pinfunction "CC1_A5") (pintype "bidirectional"))
    )
    (net (code "53") (name "Net-(U2-CC2)") (class "Default")
      (node (ref "R6") (pin "1") (pinfunction "1_1") (pintype "passive"))
      (node (ref "U2") (pin "B5") (pinfunction "CC2_B5") (pintype "bidirectional"))
    )
    (net (code "54") (name "Net-(X1-ANT)") (class "Default")
      (node (ref "L1") (pin "1") (pinfunction "1_1") (pintype "passive"))
      (node (ref "U$7") (pin "11_RF_IN") (pinfunction "11_RF_IN_11_RF_IN") (pintype "bidirectional"))
      (node (ref "X1") (pin "ANTENNA") (pinfunction "ANT_ANTENNA") (pintype "bidirectional"))
    )
    (net (code "55") (name "VBAT") (class "Default")
      (node (ref "G1") (pin "+") (pinfunction "+_+") (pintype "passive"))
      (node (ref "IC1") (pin "1") (pinfunction "VBAT_1") (pintype "power_in"))
      (node (ref "U$7") (pin "6_V_BCKP") (pinfunction "6_V_BCKP_6_V_BCKP") (pintype "bidirectional"))
    )
    (net (code "56") (name "unconnected-(SD1-DAT1-Pad8)") (class "Default")
      (node (ref "SD1") (pin "8") (pinfunction "DAT1_8") (pintype "bidirectional"))
    )
    (net (code "57") (name "unconnected-(SD1-DAT2-Pad1)") (class "Default")
      (node (ref "SD1") (pin "1") (pinfunction "DAT2_1") (pintype "bidirectional"))
    )
    (net (code "58") (name "unconnected-(SD1-~{CARD}-Pad9)") (class "Default")
      (node (ref "SD1") (pin "9") (pinfunction "~{CARD}_9") (pintype "passive"))
    )
    (net (code "59") (name "unconnected-(U$1-PadCLK)") (class "Default")
      (node (ref "U$1") (pin "CLK") (pinfunction "CLK_CLK") (pintype "bidirectional"))
    )
    (net (code "60") (name "unconnected-(U$1-PadDIO)") (class "Default")
      (node (ref "U$1") (pin "DIO") (pinfunction "DIO_DIO") (pintype "bidirectional"))
    )
    (net (code "61") (name "unconnected-(U$2-PadCLK)") (class "Default")
      (node (ref "U$2") (pin "CLK") (pinfunction "CLK_CLK") (pintype "bidirectional"))
    )
    (net (code "62") (name "unconnected-(U$2-PadDIO)") (class "Default")
      (node (ref "U$2") (pin "DIO") (pinfunction "DIO_DIO") (pintype "bidirectional"))
    )
    (net (code "63") (name "unconnected-(U$3-PadCLK)") (class "Default")
      (node (ref "U$3") (pin "CLK") (pinfunction "CLK_CLK") (pintype "bidirectional"))
    )
    (net (code "64") (name "unconnected-(U$3-PadDIO)") (class "Default")
      (node (ref "U$3") (pin "DIO") (pinfunction "DIO_DIO") (pintype "bidirectional"))
    )
    (net (code "65") (name "unconnected-(U$4-PadCLK)") (class "Default")
      (node (ref "U$4") (pin "CLK") (pinfunction "CLK_CLK") (pintype "bidirectional"))
    )
    (net (code "66") (name "unconnected-(U$4-PadDIO)") (class "Default")
      (node (ref "U$4") (pin "DIO") (pinfunction "DIO_DIO") (pintype "bidirectional"))
    )
    (net (code "67") (name "unconnected-(U$5-PadCLK)") (class "Default")
      (node (ref "U$5") (pin "CLK") (pinfunction "CLK_CLK") (pintype "bidirectional"))
    )
    (net (code "68") (name "unconnected-(U$5-PadDIO)") (class "Default")
      (node (ref "U$5") (pin "DIO") (pinfunction "DIO_DIO") (pintype "bidirectional"))
    )
    (net (code "69") (name "unconnected-(U$6-PadCLK)") (class "Default")
      (node (ref "U$6") (pin "CLK") (pinfunction "CLK_CLK") (pintype "bidirectional"))
    )
    (net (code "70") (name "unconnected-(U$6-PadDIO)") (class "Default")
      (node (ref "U$6") (pin "DIO") (pinfunction "DIO_DIO") (pintype "bidirectional"))
    )
    (net (code "71") (name "unconnected-(U$7-13_LNA_EN{slash}RES-Pad13_LNA_EN)") (class "Default")
      (node (ref "U$7") (pin "13_LNA_EN") (pinfunction "13_LNA_EN/RES_13_LNA_EN") (pintype "bidirectional"))
    )
    (net (code "72") (name "unconnected-(U$7-15_RES{slash}V_ANT-Pad15_V_ANT{slash}RESERVED)") (class "Default")
      (node (ref "U$7") (pin "15_V_ANT/RESERVED") (pinfunction "15_RES/V_ANT_15_V_ANT/RESERVED") (pintype "bidirectional"))
    )
    (net (code "73") (name "unconnected-(U$7-Pad16_SDA)") (class "Default")
      (node (ref "U$7") (pin "16_SDA") (pinfunction "16_SDA_16_SDA") (pintype "bidirectional"))
    )
    (net (code "74") (name "unconnected-(U$7-Pad17_SCL)") (class "Default")
      (node (ref "U$7") (pin "17_SCL") (pinfunction "17_SCL_17_SCL") (pintype "bidirectional"))
    )
    (net (code "75") (name "unconnected-(U$7-Pad18_SAFEBOOT_N)") (class "Default")
      (node (ref "U$7") (pin "18_SAFEBOOT_N") (pinfunction "18_SAFEBOOT_N_18_SAFEBOOT_N") (pintype "bidirectional"))
    )
    (net (code "76") (name "unconnected-(U2-SBU1-PadA8)") (class "Default")
      (node (ref "U2") (pin "A8") (pinfunction "SBU1_A8") (pintype "bidirectional"))
    )
    (net (code "77") (name "unconnected-(U2-SBU2-PadB8)") (class "Default")
      (node (ref "U2") (pin "B8") (pinfunction "SBU2_B8") (pintype "bidirectional"))
    )
  )
)
